# HF_AMP.net
KiCad netlist of a schematic drawn in Altium Designer
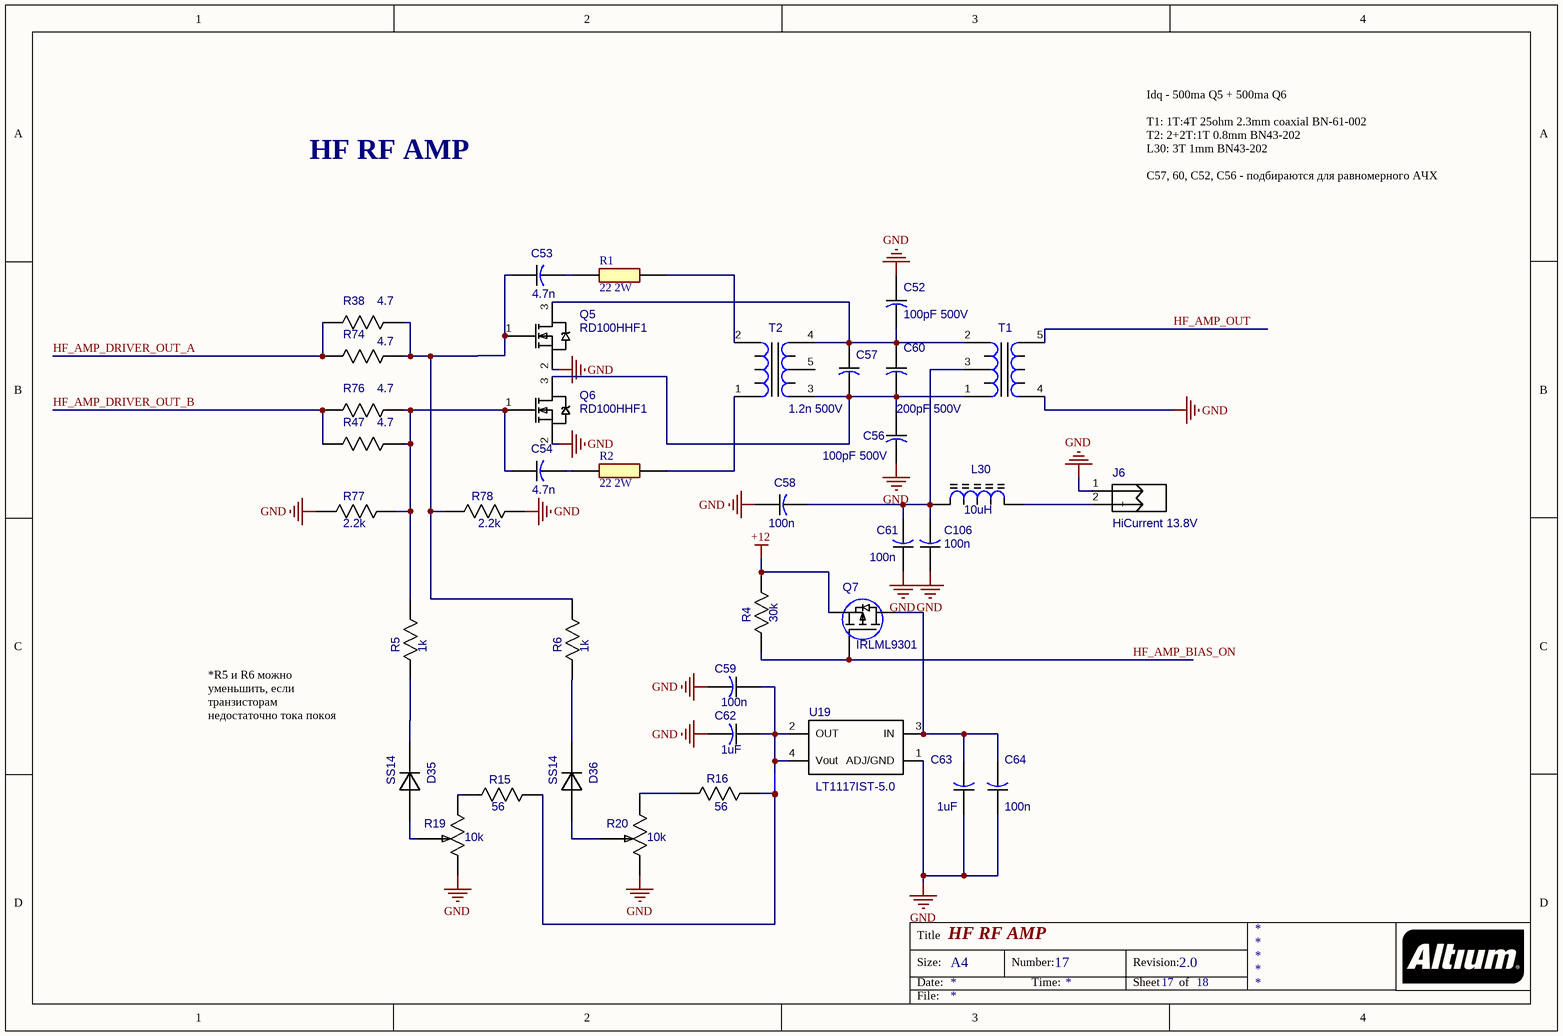
[diagram p0: HF_AMP.SchDoc]

(export (version "E")
  (design (tool "Eeschema 10.0.6"))
  (components
    (comp (ref "C52")
      (value "100pF 500V")
      (footprint "CAP_1206")
      (description "CAP_1206")
      (libsource (lib "*") (part "CAP_1206"))
    )
    (comp (ref "C53")
      (value "4.7n")
      (footprint "CAP_1206")
      (description "CAP_1206")
      (libsource (lib "*") (part "CAP_1206"))
    )
    (comp (ref "C54")
      (value "4.7n")
      (footprint "CAP_1206")
      (description "CAP_1206")
      (libsource (lib "*") (part "CAP_1206"))
    )
    (comp (ref "C56")
      (value "100pF 500V")
      (footprint "CAP_1206")
      (description "CAP_1206")
      (libsource (lib "*") (part "CAP_1206"))
    )
    (comp (ref "C57")
      (value "1.2n 500V")
      (footprint "CAP_1206")
      (description "CAP_1206")
      (libsource (lib "*") (part "CAP_1206"))
    )
    (comp (ref "C58")
      (value "100n")
      (footprint "CAP_1206")
      (description "CAP_1206")
      (libsource (lib "*") (part "CAP_1206"))
    )
    (comp (ref "C59")
      (value "100n")
      (footprint "CAP_0805")
      (description "CAP_0805")
      (libsource (lib "*") (part "CAP_0805"))
    )
    (comp (ref "C60")
      (value "200pF 500V")
      (footprint "CAP_1206")
      (description "CAP_1206")
      (libsource (lib "*") (part "CAP_1206"))
    )
    (comp (ref "C61")
      (value "100n")
      (footprint "CAP_1206")
      (description "CAP_1206")
      (libsource (lib "*") (part "CAP_1206"))
    )
    (comp (ref "C62")
      (value "1uF")
      (footprint "CAP_0805")
      (description "CAP_0805")
      (libsource (lib "*") (part "CAP_0805"))
    )
    (comp (ref "C63")
      (value "1uF")
      (footprint "CAP_0805")
      (description "CAP_0805")
      (libsource (lib "*") (part "CAP_0805"))
    )
    (comp (ref "C64")
      (value "100n")
      (footprint "CAP_0805")
      (description "CAP_0805")
      (libsource (lib "*") (part "CAP_0805"))
    )
    (comp (ref "C106")
      (value "100n")
      (footprint "CAP_1206")
      (description "CAP_1206")
      (libsource (lib "*") (part "CAP_1206"))
    )
    (comp (ref "D35") (value "SS14") (footprint "SS14") (libsource (lib "*") (part "SS14")))
    (comp (ref "D36") (value "SS14") (footprint "SS14") (libsource (lib "*") (part "SS14")))
    (comp (ref "J6")
      (value "HiCurrent 13.8V")
      (footprint "1986717-2")
      (description "JX2")
      (libsource (lib "*") (part "1986717-2"))
    )
    (comp (ref "L30")
      (value "10uH")
      (footprint "IND_FERRITE_CORE")
      (description "Inductor")
      (libsource (lib "*") (part "IND_FERRITE_CORE"))
    )
    (comp (ref "Q5")
      (value "RD100HHF1")
      (footprint "RD100_V2")
      (libsource (lib "RF-UNIT-BIG") (part "RD100HHF1"))
    )
    (comp (ref "Q6")
      (value "RD100HHF1")
      (footprint "RD100_V2")
      (libsource (lib "RF-UNIT-BIG") (part "RD100HHF1"))
    )
    (comp (ref "Q7")
      (value "IRLML9301")
      (footprint "SOT23")
      (description "MOSFET")
      (libsource (lib "*") (part "MOSFET_ENH_PD"))
    )
    (comp (ref "R1")
      (value "22 2W")
      (footprint "RES-2W")
      (description "CFR200J100R")
      (fields (field (name "MOUSER PART NUMBER") "279-CFR200J100R"))
      (libsource (lib "RF-UNIT-BIG") (part "CFR200J100R"))
    )
    (comp (ref "R2")
      (value "22 2W")
      (footprint "RES-2W")
      (description "CFR200J100R")
      (fields (field (name "MOUSER PART NUMBER") "279-CFR200J100R"))
      (libsource (lib "RF-UNIT-BIG") (part "CFR200J100R"))
    )
    (comp (ref "R4")
      (value "30k")
      (footprint "RES_0805")
      (description "RES_0805")
      (libsource (lib "*") (part "RES_0805"))
    )
    (comp (ref "R5")
      (value "1k")
      (footprint "RES_0805")
      (description "RES_0805")
      (libsource (lib "*") (part "RES_0805"))
    )
    (comp (ref "R6")
      (value "1k")
      (footprint "RES_0805")
      (description "RES_0805")
      (libsource (lib "*") (part "RES_0805"))
    )
    (comp (ref "R15")
      (value "56")
      (footprint "RES_0805")
      (description "RES_0805")
      (libsource (lib "*") (part "RES_0805"))
    )
    (comp (ref "R16")
      (value "56")
      (footprint "RES_0805")
      (description "RES_0805")
      (libsource (lib "*") (part "RES_0805"))
    )
    (comp (ref "R19")
      (value "10k")
      (footprint "3296W-1")
      (description "3296W-1-103LF")
      (fields (field (name "Comment") "ADJ-10k"))
      (libsource (lib "*") (part "306J"))
    )
    (comp (ref "R20")
      (value "10k")
      (footprint "3296W-1")
      (description "3296W-1-103LF")
      (fields (field (name "Comment") "ADJ-10k"))
      (libsource (lib "*") (part "306J"))
    )
    (comp (ref "R38")
      (value "4.7")
      (footprint "RES_1206")
      (description "RES_1206")
      (libsource (lib "*") (part "RES_1206"))
    )
    (comp (ref "R47")
      (value "4.7")
      (footprint "RES_1206")
      (description "RES_1206")
      (libsource (lib "*") (part "RES_1206"))
    )
    (comp (ref "R74")
      (value "4.7")
      (footprint "RES_1206")
      (description "RES_1206")
      (libsource (lib "*") (part "RES_1206"))
    )
    (comp (ref "R76")
      (value "4.7")
      (footprint "RES_1206")
      (description "RES_1206")
      (libsource (lib "*") (part "RES_1206"))
    )
    (comp (ref "R77")
      (value "2.2k")
      (footprint "RES_0805")
      (description "RES_0805")
      (libsource (lib "*") (part "RES_0805"))
    )
    (comp (ref "R78")
      (value "2.2k")
      (footprint "RES_0805")
      (description "RES_0805")
      (libsource (lib "*") (part "RES_0805"))
    )
    (comp (ref "T1")
      (value "TRANSF_HF2")
      (footprint "TRANSF_HF2-3")
      (libsource (lib "RF-UNIT-BIG") (part "TRANSF_RF2"))
    )
    (comp (ref "T2")
      (value "TRANSF_HF1")
      (footprint "TRANSF_HF1")
      (libsource (lib "RF-UNIT-BIG") (part "TRANSF_RF1"))
    )
    (comp (ref "U19")
      (value "LT1117IST-5.0")
      (footprint "LT1117IST-ADJ")
      (libsource (lib "*") (part "LT1117IST-ADJ"))
    )
  )
  (nets
    (net (code "1") (name "+12") (class "Default")
      (node (ref "Q7") (pin "2") (pinfunction "S_2") (pintype "passive"))
      (node (ref "R4") (pin "2") (pinfunction "2_2") (pintype "passive"))
    )
    (net (code "2") (name "/HF_AMP_BIAS_ON") (class "Default")
      (node (ref "Q7") (pin "1") (pinfunction "G_1") (pintype "passive"))
      (node (ref "R4") (pin "1") (pinfunction "1_1") (pintype "passive"))
    )
    (net (code "3") (name "/HF_AMP_DRIVER_OUT_A") (class "Default")
      (node (ref "R38") (pin "1") (pinfunction "1_1") (pintype "passive"))
      (node (ref "R74") (pin "1") (pinfunction "1_1") (pintype "passive"))
    )
    (net (code "4") (name "/HF_AMP_DRIVER_OUT_B") (class "Default")
      (node (ref "R47") (pin "1") (pinfunction "1_1") (pintype "passive"))
      (node (ref "R76") (pin "1") (pinfunction "1_1") (pintype "passive"))
    )
    (net (code "5") (name "/HF_AMP_OUT") (class "Default")
      (node (ref "T1") (pin "5") (pinfunction "S2_5") (pintype "passive"))
    )
    (net (code "6") (name "GND") (class "Default")
      (node (ref "C106") (pin "1") (pinfunction "1_1") (pintype "passive"))
      (node (ref "C52") (pin "1") (pinfunction "1_1") (pintype "passive"))
      (node (ref "C56") (pin "2") (pinfunction "2_2") (pintype "passive"))
      (node (ref "C58") (pin "1") (pinfunction "1_1") (pintype "passive"))
      (node (ref "C59") (pin "2") (pinfunction "2_2") (pintype "passive"))
      (node (ref "C61") (pin "1") (pinfunction "1_1") (pintype "passive"))
      (node (ref "C62") (pin "2") (pinfunction "2_2") (pintype "passive"))
      (node (ref "C63") (pin "1") (pinfunction "1_1") (pintype "passive"))
      (node (ref "C64") (pin "1") (pinfunction "1_1") (pintype "passive"))
      (node (ref "J6") (pin "1") (pinfunction "-_1") (pintype "passive"))
      (node (ref "Q5") (pin "2") (pinfunction "S_2") (pintype "passive"))
      (node (ref "Q6") (pin "2") (pinfunction "S_2") (pintype "passive"))
      (node (ref "R19") (pin "1") (pinfunction "CCW_1") (pintype "passive"))
      (node (ref "R20") (pin "1") (pinfunction "CCW_1") (pintype "passive"))
      (node (ref "R77") (pin "1") (pinfunction "1_1") (pintype "passive"))
      (node (ref "R78") (pin "2") (pinfunction "2_2") (pintype "passive"))
      (node (ref "T1") (pin "4") (pinfunction "S1_4") (pintype "passive"))
      (node (ref "U19") (pin "1") (pinfunction "ADJ/GND_1") (pintype "passive"))
    )
    (net (code "7") (name "Net-(C53-Pad2)") (class "Default")
      (node (ref "C53") (pin "2") (pinfunction "2_2") (pintype "passive"))
      (node (ref "R1") (pin "1") (pinfunction "1_1") (pintype "passive"))
    )
    (net (code "8") (name "Net-(C54-Pad2)") (class "Default")
      (node (ref "C54") (pin "2") (pinfunction "2_2") (pintype "passive"))
      (node (ref "R2") (pin "1") (pinfunction "1_1") (pintype "passive"))
    )
    (net (code "9") (name "Net-(D35-A)") (class "Default")
      (node (ref "D35") (pin "2") (pinfunction "A_2") (pintype "passive"))
      (node (ref "R19") (pin "2") (pinfunction "W_2") (pintype "passive"))
    )
    (net (code "10") (name "Net-(D35-K)") (class "Default")
      (node (ref "D35") (pin "1") (pinfunction "K_1") (pintype "passive"))
      (node (ref "R5") (pin "1") (pinfunction "1_1") (pintype "passive"))
    )
    (net (code "11") (name "Net-(D36-A)") (class "Default")
      (node (ref "D36") (pin "2") (pinfunction "A_2") (pintype "passive"))
      (node (ref "R20") (pin "2") (pinfunction "W_2") (pintype "passive"))
    )
    (net (code "12") (name "Net-(D36-K)") (class "Default")
      (node (ref "D36") (pin "1") (pinfunction "K_1") (pintype "passive"))
      (node (ref "R6") (pin "1") (pinfunction "1_1") (pintype "passive"))
    )
    (net (code "13") (name "Net-(J6-+)") (class "Default")
      (node (ref "J6") (pin "2") (pinfunction "+_2") (pintype "passive"))
      (node (ref "L30") (pin "2") (pinfunction "B_2") (pintype "passive"))
    )
    (net (code "14") (name "Net-(L30-A)") (class "Default")
      (node (ref "C106") (pin "2") (pinfunction "2_2") (pintype "passive"))
      (node (ref "C58") (pin "2") (pinfunction "2_2") (pintype "passive"))
      (node (ref "C61") (pin "2") (pinfunction "2_2") (pintype "passive"))
      (node (ref "L30") (pin "1") (pinfunction "A_1") (pintype "passive"))
      (node (ref "T1") (pin "3") (pinfunction "P3_3") (pintype "passive"))
    )
    (net (code "15") (name "Net-(Q5-D)") (class "Default")
      (node (ref "C52") (pin "2") (pinfunction "2_2") (pintype "passive"))
      (node (ref "C57") (pin "1") (pinfunction "1_1") (pintype "passive"))
      (node (ref "C60") (pin "1") (pinfunction "1_1") (pintype "passive"))
      (node (ref "Q5") (pin "3") (pinfunction "D_3") (pintype "passive"))
      (node (ref "T1") (pin "2") (pinfunction "P2_2") (pintype "passive"))
      (node (ref "T2") (pin "4") (pinfunction "S2_4") (pintype "passive"))
    )
    (net (code "16") (name "Net-(Q5-G)") (class "Default")
      (node (ref "C53") (pin "1") (pinfunction "1_1") (pintype "passive"))
      (node (ref "Q5") (pin "1") (pinfunction "G_1") (pintype "passive"))
      (node (ref "R38") (pin "2") (pinfunction "2_2") (pintype "passive"))
      (node (ref "R6") (pin "2") (pinfunction "2_2") (pintype "passive"))
      (node (ref "R74") (pin "2") (pinfunction "2_2") (pintype "passive"))
      (node (ref "R78") (pin "1") (pinfunction "1_1") (pintype "passive"))
    )
    (net (code "17") (name "Net-(Q6-D)") (class "Default")
      (node (ref "C56") (pin "1") (pinfunction "1_1") (pintype "passive"))
      (node (ref "C57") (pin "2") (pinfunction "2_2") (pintype "passive"))
      (node (ref "C60") (pin "2") (pinfunction "2_2") (pintype "passive"))
      (node (ref "Q6") (pin "3") (pinfunction "D_3") (pintype "passive"))
      (node (ref "T1") (pin "1") (pinfunction "P1_1") (pintype "passive"))
      (node (ref "T2") (pin "3") (pinfunction "S1_3") (pintype "passive"))
    )
    (net (code "18") (name "Net-(Q6-G)") (class "Default")
      (node (ref "C54") (pin "1") (pinfunction "1_1") (pintype "passive"))
      (node (ref "Q6") (pin "1") (pinfunction "G_1") (pintype "passive"))
      (node (ref "R47") (pin "2") (pinfunction "2_2") (pintype "passive"))
      (node (ref "R5") (pin "2") (pinfunction "2_2") (pintype "passive"))
      (node (ref "R76") (pin "2") (pinfunction "2_2") (pintype "passive"))
      (node (ref "R77") (pin "2") (pinfunction "2_2") (pintype "passive"))
    )
    (net (code "19") (name "Net-(Q7-D)") (class "Default")
      (node (ref "C63") (pin "2") (pinfunction "2_2") (pintype "passive"))
      (node (ref "C64") (pin "2") (pinfunction "2_2") (pintype "passive"))
      (node (ref "Q7") (pin "3") (pinfunction "D_3") (pintype "passive"))
      (node (ref "U19") (pin "3") (pinfunction "IN_3") (pintype "passive"))
    )
    (net (code "20") (name "Net-(R19-CW)") (class "Default")
      (node (ref "R15") (pin "1") (pinfunction "1_1") (pintype "passive"))
      (node (ref "R19") (pin "3") (pinfunction "CW_3") (pintype "passive"))
    )
    (net (code "21") (name "Net-(R20-CW)") (class "Default")
      (node (ref "R16") (pin "1") (pinfunction "1_1") (pintype "passive"))
      (node (ref "R20") (pin "3") (pinfunction "CW_3") (pintype "passive"))
    )
    (net (code "22") (name "Net-(T2-P1)") (class "Default")
      (node (ref "R2") (pin "2") (pinfunction "2_2") (pintype "passive"))
      (node (ref "T2") (pin "1") (pinfunction "P1_1") (pintype "passive"))
    )
    (net (code "23") (name "Net-(T2-P2)") (class "Default")
      (node (ref "R1") (pin "2") (pinfunction "2_2") (pintype "passive"))
      (node (ref "T2") (pin "2") (pinfunction "P2_2") (pintype "passive"))
    )
    (net (code "24") (name "Net-(U19-OUT)") (class "Default")
      (node (ref "C59") (pin "1") (pinfunction "1_1") (pintype "passive"))
      (node (ref "C62") (pin "1") (pinfunction "1_1") (pintype "passive"))
      (node (ref "R15") (pin "2") (pinfunction "2_2") (pintype "passive"))
      (node (ref "R16") (pin "2") (pinfunction "2_2") (pintype "passive"))
      (node (ref "U19") (pin "2") (pinfunction "OUT_2") (pintype "passive"))
      (node (ref "U19") (pin "4") (pinfunction "Vout_4") (pintype "passive"))
    )
    (net (code "25") (name "unconnected-(T2-S3-Pad5)") (class "Default")
      (node (ref "T2") (pin "5") (pinfunction "S3_5") (pintype "passive"))
    )
  )
)
